# MCU.net
KiCad netlist of a schematic drawn in Altium Designer
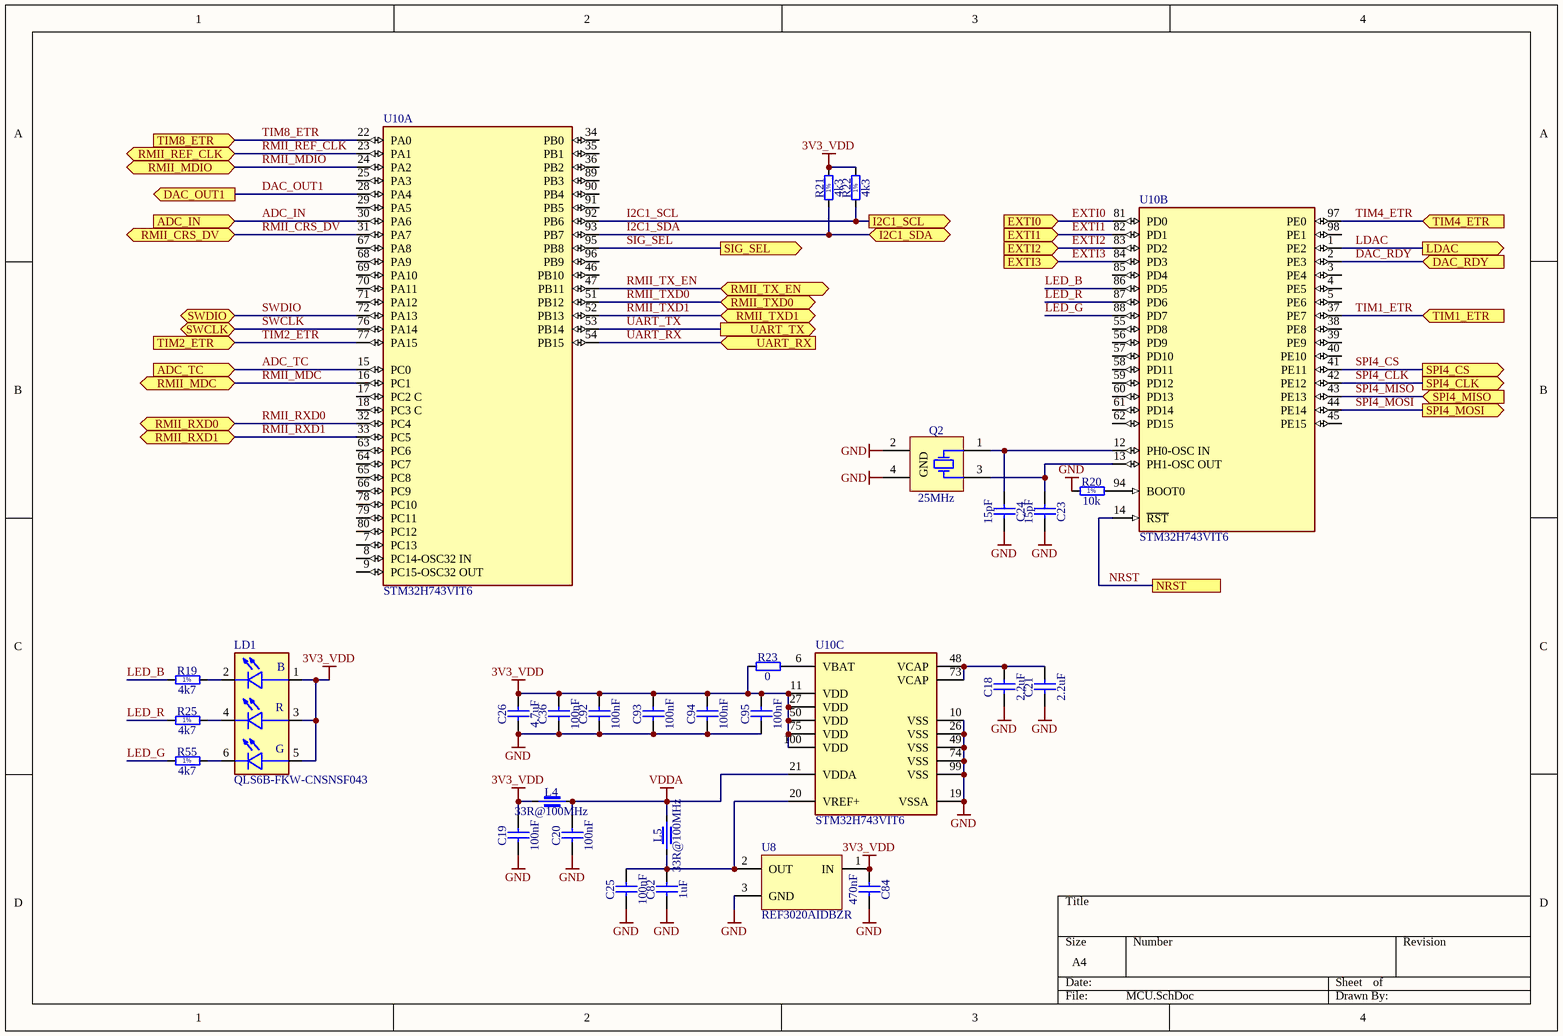
[diagram p0: MCU.SchDoc]

(export (version "E")
  (design (tool "Eeschema 10.0.6"))
  (components
    (comp (ref "C18")
      (value "2.2uF")
      (footprint "CAPC1608X87N")
      (description "Non-polarised capacitor")
      (fields
        (field (name "PART NUMBER") "CC0603_2.2UF_16V_10%_X5R")
        (field (name "VOLTAGE") "16V")
        (field (name "AUTHOR") "CERN DEM JLC")
      )
      (libsource (lib "Capacitors") (part "Capacitor - non polarized"))
    )
    (comp (ref "C19")
      (value "100nF")
      (footprint "CAPC1005X55N")
      (description "Non-polarised capacitor")
      (fields
        (field (name "PART NUMBER") "CC0402_100NF_16V_10%_X7R")
        (field (name "VOLTAGE") "16V")
        (field (name "AUTHOR") "CERN DEM JLC")
      )
      (libsource (lib "Capacitors") (part "Capacitor - non polarized"))
    )
    (comp (ref "C20")
      (value "100nF")
      (footprint "CAPC1005X55N")
      (description "Non-polarised capacitor")
      (fields
        (field (name "PART NUMBER") "CC0402_100NF_16V_10%_X7R")
        (field (name "VOLTAGE") "16V")
        (field (name "AUTHOR") "CERN DEM JLC")
      )
      (libsource (lib "Capacitors") (part "Capacitor - non polarized"))
    )
    (comp (ref "C21")
      (value "2.2uF")
      (footprint "CAPC1608X87N")
      (description "Non-polarised capacitor")
      (fields
        (field (name "PART NUMBER") "CC0603_2.2UF_16V_10%_X5R")
        (field (name "VOLTAGE") "16V")
        (field (name "AUTHOR") "CERN DEM JLC")
      )
      (libsource (lib "Capacitors") (part "Capacitor - non polarized"))
    )
    (comp (ref "C23")
      (value "15pF")
      (footprint "CAPC1005X55N")
      (description "Non-polarised capacitor")
      (fields
        (field (name "PART NUMBER") "CC0402_15PF_50V_5%_C0G")
        (field (name "VOLTAGE") "50V")
        (field (name "AUTHOR") "CERN DEM JLC")
      )
      (libsource (lib "Capacitors") (part "Capacitor - non polarized"))
    )
    (comp (ref "C24")
      (value "15pF")
      (footprint "CAPC1005X55N")
      (description "Non-polarised capacitor")
      (fields
        (field (name "PART NUMBER") "CC0402_15PF_50V_5%_C0G")
        (field (name "VOLTAGE") "50V")
        (field (name "AUTHOR") "CERN DEM JLC")
      )
      (libsource (lib "Capacitors") (part "Capacitor - non polarized"))
    )
    (comp (ref "C25")
      (value "100nF")
      (footprint "CAPC1005X55N")
      (description "Non-polarised capacitor")
      (fields
        (field (name "PART NUMBER") "CC0402_100NF_16V_10%_X7R")
        (field (name "VOLTAGE") "16V")
        (field (name "AUTHOR") "CERN DEM JLC")
      )
      (libsource (lib "Capacitors") (part "Capacitor - non polarized"))
    )
    (comp (ref "C26")
      (value "4.7uF")
      (footprint "CAPC1709X95N")
      (description "Non-polarised capacitor")
      (fields
        (field (name "PART NUMBER") "CC0603_4.7UF_16V_10%_X5R")
        (field (name "VOLTAGE") "16V")
        (field (name "AUTHOR") "CERN DEM JLC")
      )
      (libsource (lib "Capacitors") (part "Capacitor - non polarized"))
    )
    (comp (ref "C36")
      (value "100nF")
      (footprint "CAPC1005X55N")
      (description "Non-polarised capacitor")
      (fields
        (field (name "PART NUMBER") "CC0402_100NF_16V_10%_X7R")
        (field (name "VOLTAGE") "16V")
        (field (name "AUTHOR") "CERN DEM JLC")
      )
      (libsource (lib "Capacitors") (part "Capacitor - non polarized"))
    )
    (comp (ref "C82")
      (value "1uF")
      (footprint "CAPC1005X55N")
      (description "Non-polarised capacitor")
      (fields
        (field (name "PART NUMBER") "CC0402_1UF_16V_10%_X5R")
        (field (name "VOLTAGE") "16V")
        (field (name "AUTHOR") "CERN DEM JLC")
      )
      (libsource (lib "Capacitors") (part "Capacitor - non polarized"))
    )
    (comp (ref "C84")
      (value "470nF")
      (footprint "CAPC1005X55N")
      (description "Non-polarised capacitor")
      (fields
        (field (name "PART NUMBER") "CC0402_470NF_16V_10%_X5R")
        (field (name "VOLTAGE") "16V")
        (field (name "AUTHOR") "CERN DEM JLC")
      )
      (libsource (lib "Capacitors") (part "Capacitor - non polarized"))
    )
    (comp (ref "C92")
      (value "100nF")
      (footprint "CAPC1005X55N")
      (description "Non-polarised capacitor")
      (fields
        (field (name "PART NUMBER") "CC0402_100NF_16V_10%_X7R")
        (field (name "VOLTAGE") "16V")
        (field (name "AUTHOR") "CERN DEM JLC")
      )
      (libsource (lib "Capacitors") (part "Capacitor - non polarized"))
    )
    (comp (ref "C93")
      (value "100nF")
      (footprint "CAPC1005X55N")
      (description "Non-polarised capacitor")
      (fields
        (field (name "PART NUMBER") "CC0402_100NF_16V_10%_X7R")
        (field (name "VOLTAGE") "16V")
        (field (name "AUTHOR") "CERN DEM JLC")
      )
      (libsource (lib "Capacitors") (part "Capacitor - non polarized"))
    )
    (comp (ref "C94")
      (value "100nF")
      (footprint "CAPC1005X55N")
      (description "Non-polarised capacitor")
      (fields
        (field (name "PART NUMBER") "CC0402_100NF_16V_10%_X7R")
        (field (name "VOLTAGE") "16V")
        (field (name "AUTHOR") "CERN DEM JLC")
      )
      (libsource (lib "Capacitors") (part "Capacitor - non polarized"))
    )
    (comp (ref "C95")
      (value "100nF")
      (footprint "CAPC1005X55N")
      (description "Non-polarised capacitor")
      (fields
        (field (name "PART NUMBER") "CC0402_100NF_16V_10%_X7R")
        (field (name "VOLTAGE") "16V")
        (field (name "AUTHOR") "CERN DEM JLC")
      )
      (libsource (lib "Capacitors") (part "Capacitor - non polarized"))
    )
    (comp (ref "L4")
      (value "33R@100MHz")
      (footprint "INDC1005X55N")
      (fields
        (field (name "PART NUMBER") "IND0402_MURATA_BLM15PX330SN1D")
        (field (name "POWER") "3A")
        (field (name "TOLERANCE") "±25%")
        (field (name "AUTHOR") "CERN DEM JMW")
      )
      (libsource (lib "") (part "Ferrite Bead_1"))
    )
    (comp (ref "L5")
      (value "33R@100MHz")
      (footprint "INDC1005X55N")
      (fields
        (field (name "PART NUMBER") "IND0402_MURATA_BLM15PX330SN1D")
        (field (name "POWER") "3A")
        (field (name "TOLERANCE") "±25%")
        (field (name "AUTHOR") "CERN DEM JMW")
      )
      (libsource (lib "Inductors & Transformers") (part "Ferrite Bead"))
    )
    (comp (ref "LD1")
      (value "QLS6B-FKW-CNSNSF043")
      (footprint "LED_QLS6B-FKW-CNSNSF043")
      (fields (field (name "MF") "Cree Inc."))
      (libsource (lib "QLS6B-FKW-CNSNSF043") (part "QLS6B-FKW-CNSNSF043"))
    )
    (comp (ref "Q2")
      (value "25MHz")
      (footprint "XTAL_EPSON_TSX-3225")
      (description "Crystal 4 pins 1=XTAL Control 2=GND3=XTAL 4=GND")
      (fields
        (field (name "PART NUMBER") "XTAL_25MHZ_EPSON_TSX-3225 25.0000MF10Z-AC")
        (field (name "MANUFACTURER") "EPSON")
        (field (name "AUTHOR") "CERN DEM JLC")
      )
      (libsource (lib "ICs And Semiconductors") (part "Quartz Crystal 1X 2GND 3X 4GND"))
    )
    (comp (ref "R19")
      (value "4k7")
      (footprint "RESC1005X40N")
      (description "Resistor - 1%")
      (fields
        (field (name "PART NUMBER") "R0402_4K7_1%_0.0625W_100PPM")
        (field (name "POWER") "0.0625W")
        (field (name "AUTHOR") "CERN DEM JLC")
      )
      (libsource (lib "Resistors") (part "Resistor - 1%"))
    )
    (comp (ref "R20")
      (value "10k")
      (footprint "RESC1005X40N")
      (description "Resistor - 1%")
      (fields
        (field (name "PART NUMBER") "R0402_10K_1%_0.0625W_100PPM")
        (field (name "POWER") "0.0625W")
        (field (name "AUTHOR") "CERN DEM JLC")
      )
      (libsource (lib "Resistors") (part "Resistor - 1%"))
    )
    (comp (ref "R21")
      (value "4k3")
      (footprint "RESC1005X40N")
      (description "Resistor - 1%")
      (fields
        (field (name "PART NUMBER") "R0402_4K3_1%_0.0625W_100PPM")
        (field (name "POWER") "0.0625W")
        (field (name "AUTHOR") "CERN DEM JLC")
      )
      (libsource (lib "Resistors") (part "Resistor - 1%"))
    )
    (comp (ref "R22")
      (value "4k3")
      (footprint "RESC1005X40N")
      (description "Resistor - 1%")
      (fields
        (field (name "PART NUMBER") "R0402_4K3_1%_0.0625W_100PPM")
        (field (name "POWER") "0.0625W")
        (field (name "AUTHOR") "CERN DEM JLC")
      )
      (libsource (lib "Resistors") (part "Resistor - 1%"))
    )
    (comp (ref "R23")
      (value "0")
      (footprint "RESC1005X40N")
      (description "Resistor")
      (fields
        (field (name "PART NUMBER") "R0402_0R_JUMPER")
        (field (name "MANUFACTURER") "GENERIC")
        (field (name "AUTHOR") "CERN DEM JLC")
      )
      (libsource (lib "Resistors") (part "Resistor"))
    )
    (comp (ref "R25")
      (value "4k7")
      (footprint "RESC1005X40N")
      (description "Resistor - 1%")
      (fields
        (field (name "PART NUMBER") "R0402_4K7_1%_0.0625W_100PPM")
        (field (name "POWER") "0.0625W")
        (field (name "AUTHOR") "CERN DEM JLC")
      )
      (libsource (lib "Resistors") (part "Resistor - 1%"))
    )
    (comp (ref "R55")
      (value "4k7")
      (footprint "RESC1005X40N")
      (description "Resistor - 1%")
      (fields
        (field (name "PART NUMBER") "R0402_4K7_1%_0.0625W_100PPM")
        (field (name "POWER") "0.0625W")
        (field (name "AUTHOR") "CERN DEM JLC")
      )
      (libsource (lib "Resistors") (part "Resistor - 1%"))
    )
    (comp (ref "U8")
      (value "REF3020AIDBZR")
      (footprint "DBZ0003A_L")
      (fields (field (name "MANUFACTURER") "Texas Instruments"))
      (libsource (lib "Altium Content Vault") (part "TI-REF3020DBZ3"))
    )
    (comp (ref "U10")
      (value "STM32H743VIT6")
      (footprint "FP-LQFP100-1L-MFG")
      (description "IC MCU 32BIT 2MB FLASH 100LQFP")
      (fields
        (field (name "OCTOPART") "https://octopart.com/stm32h743vit6-stmicroelectronics-76372527")
        (field (name "MANUFACTURER") "STMicroelectronics")
      )
      (libsource (lib "Altium Content Vault") (part "01082ce2885d1d16a22823c45526fe6"))
    )
  )
  (nets
    (net (code "1") (name "/ADC_IN") (class "Default")
      (node (ref "U10") (pin "30") (pinfunction "PA6_30") (pintype "bidirectional"))
    )
    (net (code "2") (name "/ADC_TC") (class "Default")
      (node (ref "U10") (pin "15") (pinfunction "PC0_15") (pintype "bidirectional"))
    )
    (net (code "3") (name "/DAC_OUT1") (class "Default")
      (node (ref "U10") (pin "28") (pinfunction "PA4_28") (pintype "bidirectional"))
    )
    (net (code "4") (name "/DAC_RDY") (class "Default")
      (node (ref "U10") (pin "2") (pinfunction "PE3_2") (pintype "bidirectional"))
    )
    (net (code "5") (name "/EXTI0") (class "Default")
      (node (ref "U10") (pin "81") (pinfunction "PD0_81") (pintype "bidirectional"))
    )
    (net (code "6") (name "/EXTI1") (class "Default")
      (node (ref "U10") (pin "82") (pinfunction "PD1_82") (pintype "bidirectional"))
    )
    (net (code "7") (name "/EXTI2") (class "Default")
      (node (ref "U10") (pin "83") (pinfunction "PD2_83") (pintype "bidirectional"))
    )
    (net (code "8") (name "/EXTI3") (class "Default")
      (node (ref "U10") (pin "84") (pinfunction "PD3_84") (pintype "bidirectional"))
    )
    (net (code "9") (name "/I2C1_SCL") (class "Default")
      (node (ref "R22") (pin "1") (pinfunction "1_1") (pintype "passive"))
      (node (ref "U10") (pin "92") (pinfunction "PB6_92") (pintype "bidirectional"))
    )
    (net (code "10") (name "/I2C1_SDA") (class "Default")
      (node (ref "R21") (pin "1") (pinfunction "1_1") (pintype "passive"))
      (node (ref "U10") (pin "93") (pinfunction "PB7_93") (pintype "bidirectional"))
    )
    (net (code "11") (name "/LDAC") (class "Default")
      (node (ref "U10") (pin "1") (pinfunction "PE2_1") (pintype "bidirectional"))
    )
    (net (code "12") (name "/LED_B") (class "Default")
      (node (ref "R19") (pin "1") (pinfunction "1_1") (pintype "passive"))
      (node (ref "U10") (pin "86") (pinfunction "PD5_86") (pintype "bidirectional"))
    )
    (net (code "13") (name "/LED_G") (class "Default")
      (node (ref "R55") (pin "1") (pinfunction "1_1") (pintype "passive"))
      (node (ref "U10") (pin "88") (pinfunction "PD7_88") (pintype "bidirectional"))
    )
    (net (code "14") (name "/LED_R") (class "Default")
      (node (ref "R25") (pin "1") (pinfunction "1_1") (pintype "passive"))
      (node (ref "U10") (pin "87") (pinfunction "PD6_87") (pintype "bidirectional"))
    )
    (net (code "15") (name "/NRST") (class "Default")
      (node (ref "U10") (pin "14") (pinfunction "~{RST}_14") (pintype "input"))
    )
    (net (code "16") (name "/RMII_CRS_DV") (class "Default")
      (node (ref "U10") (pin "31") (pinfunction "PA7_31") (pintype "bidirectional"))
    )
    (net (code "17") (name "/RMII_MDC") (class "Default")
      (node (ref "U10") (pin "16") (pinfunction "PC1_16") (pintype "bidirectional"))
    )
    (net (code "18") (name "/RMII_MDIO") (class "Default")
      (node (ref "U10") (pin "24") (pinfunction "PA2_24") (pintype "bidirectional"))
    )
    (net (code "19") (name "/RMII_REF_CLK") (class "Default")
      (node (ref "U10") (pin "23") (pinfunction "PA1_23") (pintype "bidirectional"))
    )
    (net (code "20") (name "/RMII_RXD0") (class "Default")
      (node (ref "U10") (pin "32") (pinfunction "PC4_32") (pintype "bidirectional"))
    )
    (net (code "21") (name "/RMII_RXD1") (class "Default")
      (node (ref "U10") (pin "33") (pinfunction "PC5_33") (pintype "bidirectional"))
    )
    (net (code "22") (name "/RMII_TXD0") (class "Default")
      (node (ref "U10") (pin "51") (pinfunction "PB12_51") (pintype "bidirectional"))
    )
    (net (code "23") (name "/RMII_TXD1") (class "Default")
      (node (ref "U10") (pin "52") (pinfunction "PB13_52") (pintype "bidirectional"))
    )
    (net (code "24") (name "/RMII_TX_EN") (class "Default")
      (node (ref "U10") (pin "47") (pinfunction "PB11_47") (pintype "bidirectional"))
    )
    (net (code "25") (name "/SIG_SEL") (class "Default")
      (node (ref "U10") (pin "95") (pinfunction "PB8_95") (pintype "bidirectional"))
    )
    (net (code "26") (name "/SPI4_CLK") (class "Default")
      (node (ref "U10") (pin "42") (pinfunction "PE12_42") (pintype "bidirectional"))
    )
    (net (code "27") (name "/SPI4_CS") (class "Default")
      (node (ref "U10") (pin "41") (pinfunction "PE11_41") (pintype "bidirectional"))
    )
    (net (code "28") (name "/SPI4_MISO") (class "Default")
      (node (ref "U10") (pin "43") (pinfunction "PE13_43") (pintype "bidirectional"))
    )
    (net (code "29") (name "/SPI4_MOSI") (class "Default")
      (node (ref "U10") (pin "44") (pinfunction "PE14_44") (pintype "bidirectional"))
    )
    (net (code "30") (name "/SWCLK") (class "Default")
      (node (ref "U10") (pin "76") (pinfunction "PA14_76") (pintype "bidirectional"))
    )
    (net (code "31") (name "/SWDIO") (class "Default")
      (node (ref "U10") (pin "72") (pinfunction "PA13_72") (pintype "bidirectional"))
    )
    (net (code "32") (name "/TIM1_ETR") (class "Default")
      (node (ref "U10") (pin "37") (pinfunction "PE7_37") (pintype "bidirectional"))
    )
    (net (code "33") (name "/TIM2_ETR") (class "Default")
      (node (ref "U10") (pin "77") (pinfunction "PA15_77") (pintype "bidirectional"))
    )
    (net (code "34") (name "/TIM4_ETR") (class "Default")
      (node (ref "U10") (pin "97") (pinfunction "PE0_97") (pintype "bidirectional"))
    )
    (net (code "35") (name "/TIM8_ETR") (class "Default")
      (node (ref "U10") (pin "22") (pinfunction "PA0_22") (pintype "bidirectional"))
    )
    (net (code "36") (name "/UART_RX") (class "Default")
      (node (ref "U10") (pin "54") (pinfunction "PB15_54") (pintype "bidirectional"))
    )
    (net (code "37") (name "/UART_TX") (class "Default")
      (node (ref "U10") (pin "53") (pinfunction "PB14_53") (pintype "bidirectional"))
    )
    (net (code "38") (name "3V3_VDD") (class "Default")
      (node (ref "C19") (pin "2") (pinfunction "2_2") (pintype "passive"))
      (node (ref "C26") (pin "2") (pinfunction "2_2") (pintype "passive"))
      (node (ref "C36") (pin "2") (pinfunction "2_2") (pintype "passive"))
      (node (ref "C84") (pin "2") (pinfunction "2_2") (pintype "passive"))
      (node (ref "C92") (pin "2") (pinfunction "2_2") (pintype "passive"))
      (node (ref "C93") (pin "2") (pinfunction "2_2") (pintype "passive"))
      (node (ref "C94") (pin "2") (pinfunction "2_2") (pintype "passive"))
      (node (ref "C95") (pin "2") (pinfunction "2_2") (pintype "passive"))
      (node (ref "L4") (pin "1") (pinfunction "1_1") (pintype "passive"))
      (node (ref "LD1") (pin "1") (pinfunction "BLUE_ANODE_1") (pintype "passive"))
      (node (ref "LD1") (pin "3") (pinfunction "RED_ANODE_3") (pintype "passive"))
      (node (ref "LD1") (pin "5") (pinfunction "GREEN_ANODE_5") (pintype "passive"))
      (node (ref "R21") (pin "2") (pinfunction "2_2") (pintype "passive"))
      (node (ref "R22") (pin "2") (pinfunction "2_2") (pintype "passive"))
      (node (ref "R23") (pin "1") (pinfunction "1_1") (pintype "passive"))
      (node (ref "U10") (pin "100") (pinfunction "VDD_100") (pintype "power_in"))
      (node (ref "U10") (pin "11") (pinfunction "VDD_11") (pintype "power_in"))
      (node (ref "U10") (pin "27") (pinfunction "VDD_27") (pintype "power_in"))
      (node (ref "U10") (pin "50") (pinfunction "VDD_50") (pintype "power_in"))
      (node (ref "U10") (pin "75") (pinfunction "VDD_75") (pintype "power_in"))
      (node (ref "U8") (pin "1") (pinfunction "IN_1") (pintype "power_in"))
    )
    (net (code "39") (name "GND") (class "Default")
      (node (ref "C18") (pin "1") (pinfunction "1_1") (pintype "passive"))
      (node (ref "C19") (pin "1") (pinfunction "1_1") (pintype "passive"))
      (node (ref "C20") (pin "1") (pinfunction "1_1") (pintype "passive"))
      (node (ref "C21") (pin "1") (pinfunction "1_1") (pintype "passive"))
      (node (ref "C23") (pin "1") (pinfunction "1_1") (pintype "passive"))
      (node (ref "C24") (pin "1") (pinfunction "1_1") (pintype "passive"))
      (node (ref "C25") (pin "1") (pinfunction "1_1") (pintype "passive"))
      (node (ref "C26") (pin "1") (pinfunction "1_1") (pintype "passive"))
      (node (ref "C36") (pin "1") (pinfunction "1_1") (pintype "passive"))
      (node (ref "C82") (pin "1") (pinfunction "1_1") (pintype "passive"))
      (node (ref "C84") (pin "1") (pinfunction "1_1") (pintype "passive"))
      (node (ref "C92") (pin "1") (pinfunction "1_1") (pintype "passive"))
      (node (ref "C93") (pin "1") (pinfunction "1_1") (pintype "passive"))
      (node (ref "C94") (pin "1") (pinfunction "1_1") (pintype "passive"))
      (node (ref "C95") (pin "1") (pinfunction "1_1") (pintype "passive"))
      (node (ref "Q2") (pin "2") (pinfunction "GND_2") (pintype "power_in"))
      (node (ref "Q2") (pin "4") (pinfunction "GND_4") (pintype "power_in"))
      (node (ref "R20") (pin "1") (pinfunction "1_1") (pintype "passive"))
      (node (ref "U10") (pin "10") (pinfunction "VSS_10") (pintype "power_in"))
      (node (ref "U10") (pin "19") (pinfunction "VSSA_19") (pintype "power_in"))
      (node (ref "U10") (pin "26") (pinfunction "VSS_26") (pintype "power_in"))
      (node (ref "U10") (pin "49") (pinfunction "VSS_49") (pintype "power_in"))
      (node (ref "U10") (pin "74") (pinfunction "VSS_74") (pintype "power_in"))
      (node (ref "U10") (pin "99") (pinfunction "VSS_99") (pintype "power_in"))
      (node (ref "U8") (pin "3") (pinfunction "GND_3") (pintype "power_in"))
    )
    (net (code "40") (name "Net-(C18-Pad2)") (class "Default")
      (node (ref "C18") (pin "2") (pinfunction "2_2") (pintype "passive"))
      (node (ref "C21") (pin "2") (pinfunction "2_2") (pintype "passive"))
      (node (ref "U10") (pin "48") (pinfunction "VCAP_48") (pintype "passive"))
      (node (ref "U10") (pin "73") (pinfunction "VCAP_73") (pintype "passive"))
    )
    (net (code "41") (name "Net-(LD1-BLUE_CATHODE)") (class "Default")
      (node (ref "LD1") (pin "2") (pinfunction "BLUE_CATHODE_2") (pintype "passive"))
      (node (ref "R19") (pin "2") (pinfunction "2_2") (pintype "passive"))
    )
    (net (code "42") (name "Net-(LD1-GREEN_CATHODE)") (class "Default")
      (node (ref "LD1") (pin "6") (pinfunction "GREEN_CATHODE_6") (pintype "passive"))
      (node (ref "R55") (pin "2") (pinfunction "2_2") (pintype "passive"))
    )
    (net (code "43") (name "Net-(LD1-RED_CATHODE)") (class "Default")
      (node (ref "LD1") (pin "4") (pinfunction "RED_CATHODE_4") (pintype "passive"))
      (node (ref "R25") (pin "2") (pinfunction "2_2") (pintype "passive"))
    )
    (net (code "44") (name "Net-(U10B-BOOT0)") (class "Default")
      (node (ref "R20") (pin "2") (pinfunction "2_2") (pintype "passive"))
      (node (ref "U10") (pin "94") (pinfunction "BOOT0_94") (pintype "input"))
    )
    (net (code "45") (name "Net-(U10B-PH0-OSC_IN)") (class "Default")
      (node (ref "C24") (pin "2") (pinfunction "2_2") (pintype "passive"))
      (node (ref "Q2") (pin "1") (pinfunction "X_1") (pintype "passive"))
      (node (ref "U10") (pin "12") (pinfunction "PH0-OSC_IN_12") (pintype "bidirectional"))
    )
    (net (code "46") (name "Net-(U10B-PH1-OSC_OUT)") (class "Default")
      (node (ref "C23") (pin "2") (pinfunction "2_2") (pintype "passive"))
      (node (ref "Q2") (pin "3") (pinfunction "X_3") (pintype "passive"))
      (node (ref "U10") (pin "13") (pinfunction "PH1-OSC_OUT_13") (pintype "bidirectional"))
    )
    (net (code "47") (name "Net-(U10C-VBAT)") (class "Default")
      (node (ref "R23") (pin "2") (pinfunction "2_2") (pintype "passive"))
      (node (ref "U10") (pin "6") (pinfunction "VBAT_6") (pintype "power_in"))
    )
    (net (code "48") (name "Net-(U10C-VREF+)") (class "Default")
      (node (ref "C25") (pin "2") (pinfunction "2_2") (pintype "passive"))
      (node (ref "C82") (pin "2") (pinfunction "2_2") (pintype "passive"))
      (node (ref "L5") (pin "1") (pinfunction "1_1") (pintype "passive"))
      (node (ref "U10") (pin "20") (pinfunction "VREF+_20") (pintype "power_in"))
      (node (ref "U8") (pin "2") (pinfunction "OUT_2") (pintype "power_in"))
    )
    (net (code "49") (name "VDDA") (class "Default")
      (node (ref "C20") (pin "2") (pinfunction "2_2") (pintype "passive"))
      (node (ref "L4") (pin "2") (pinfunction "2_2") (pintype "passive"))
      (node (ref "L5") (pin "2") (pinfunction "2_2") (pintype "passive"))
      (node (ref "U10") (pin "21") (pinfunction "VDDA_21") (pintype "power_in"))
    )
    (net (code "50") (name "unconnected-(U10A-PA3-Pad25)") (class "Default")
      (node (ref "U10") (pin "25") (pinfunction "PA3_25") (pintype "bidirectional"))
    )
    (net (code "51") (name "unconnected-(U10A-PA5-Pad29)") (class "Default")
      (node (ref "U10") (pin "29") (pinfunction "PA5_29") (pintype "bidirectional"))
    )
    (net (code "52") (name "unconnected-(U10A-PA8-Pad67)") (class "Default")
      (node (ref "U10") (pin "67") (pinfunction "PA8_67") (pintype "bidirectional"))
    )
    (net (code "53") (name "unconnected-(U10A-PA9-Pad68)") (class "Default")
      (node (ref "U10") (pin "68") (pinfunction "PA9_68") (pintype "bidirectional"))
    )
    (net (code "54") (name "unconnected-(U10A-PA10-Pad69)") (class "Default")
      (node (ref "U10") (pin "69") (pinfunction "PA10_69") (pintype "bidirectional"))
    )
    (net (code "55") (name "unconnected-(U10A-PA11-Pad70)") (class "Default")
      (node (ref "U10") (pin "70") (pinfunction "PA11_70") (pintype "bidirectional"))
    )
    (net (code "56") (name "unconnected-(U10A-PA12-Pad71)") (class "Default")
      (node (ref "U10") (pin "71") (pinfunction "PA12_71") (pintype "bidirectional"))
    )
    (net (code "57") (name "unconnected-(U10A-PB0-Pad34)") (class "Default")
      (node (ref "U10") (pin "34") (pinfunction "PB0_34") (pintype "bidirectional"))
    )
    (net (code "58") (name "unconnected-(U10A-PB1-Pad35)") (class "Default")
      (node (ref "U10") (pin "35") (pinfunction "PB1_35") (pintype "bidirectional"))
    )
    (net (code "59") (name "unconnected-(U10A-PB2-Pad36)") (class "Default")
      (node (ref "U10") (pin "36") (pinfunction "PB2_36") (pintype "bidirectional"))
    )
    (net (code "60") (name "unconnected-(U10A-PB3-Pad89)") (class "Default")
      (node (ref "U10") (pin "89") (pinfunction "PB3_89") (pintype "bidirectional"))
    )
    (net (code "61") (name "unconnected-(U10A-PB4-Pad90)") (class "Default")
      (node (ref "U10") (pin "90") (pinfunction "PB4_90") (pintype "bidirectional"))
    )
    (net (code "62") (name "unconnected-(U10A-PB5-Pad91)") (class "Default")
      (node (ref "U10") (pin "91") (pinfunction "PB5_91") (pintype "bidirectional"))
    )
    (net (code "63") (name "unconnected-(U10A-PB9-Pad96)") (class "Default")
      (node (ref "U10") (pin "96") (pinfunction "PB9_96") (pintype "bidirectional"))
    )
    (net (code "64") (name "unconnected-(U10A-PB10-Pad46)") (class "Default")
      (node (ref "U10") (pin "46") (pinfunction "PB10_46") (pintype "bidirectional"))
    )
    (net (code "65") (name "unconnected-(U10A-PC2_C-Pad17)") (class "Default")
      (node (ref "U10") (pin "17") (pinfunction "PC2_C_17") (pintype "bidirectional"))
    )
    (net (code "66") (name "unconnected-(U10A-PC3_C-Pad18)") (class "Default")
      (node (ref "U10") (pin "18") (pinfunction "PC3_C_18") (pintype "bidirectional"))
    )
    (net (code "67") (name "unconnected-(U10A-PC6-Pad63)") (class "Default")
      (node (ref "U10") (pin "63") (pinfunction "PC6_63") (pintype "bidirectional"))
    )
    (net (code "68") (name "unconnected-(U10A-PC7-Pad64)") (class "Default")
      (node (ref "U10") (pin "64") (pinfunction "PC7_64") (pintype "bidirectional"))
    )
    (net (code "69") (name "unconnected-(U10A-PC8-Pad65)") (class "Default")
      (node (ref "U10") (pin "65") (pinfunction "PC8_65") (pintype "bidirectional"))
    )
    (net (code "70") (name "unconnected-(U10A-PC9-Pad66)") (class "Default")
      (node (ref "U10") (pin "66") (pinfunction "PC9_66") (pintype "bidirectional"))
    )
    (net (code "71") (name "unconnected-(U10A-PC10-Pad78)") (class "Default")
      (node (ref "U10") (pin "78") (pinfunction "PC10_78") (pintype "bidirectional"))
    )
    (net (code "72") (name "unconnected-(U10A-PC11-Pad79)") (class "Default")
      (node (ref "U10") (pin "79") (pinfunction "PC11_79") (pintype "bidirectional"))
    )
    (net (code "73") (name "unconnected-(U10A-PC12-Pad80)") (class "Default")
      (node (ref "U10") (pin "80") (pinfunction "PC12_80") (pintype "bidirectional"))
    )
    (net (code "74") (name "unconnected-(U10A-PC13-Pad7)") (class "Default")
      (node (ref "U10") (pin "7") (pinfunction "PC13_7") (pintype "bidirectional"))
    )
    (net (code "75") (name "unconnected-(U10A-PC14-OSC32_IN-Pad8)") (class "Default")
      (node (ref "U10") (pin "8") (pinfunction "PC14-OSC32_IN_8") (pintype "bidirectional"))
    )
    (net (code "76") (name "unconnected-(U10A-PC15-OSC32_OUT-Pad9)") (class "Default")
      (node (ref "U10") (pin "9") (pinfunction "PC15-OSC32_OUT_9") (pintype "bidirectional"))
    )
    (net (code "77") (name "unconnected-(U10B-PD4-Pad85)") (class "Default")
      (node (ref "U10") (pin "85") (pinfunction "PD4_85") (pintype "bidirectional"))
    )
    (net (code "78") (name "unconnected-(U10B-PD8-Pad55)") (class "Default")
      (node (ref "U10") (pin "55") (pinfunction "PD8_55") (pintype "bidirectional"))
    )
    (net (code "79") (name "unconnected-(U10B-PD9-Pad56)") (class "Default")
      (node (ref "U10") (pin "56") (pinfunction "PD9_56") (pintype "bidirectional"))
    )
    (net (code "80") (name "unconnected-(U10B-PD10-Pad57)") (class "Default")
      (node (ref "U10") (pin "57") (pinfunction "PD10_57") (pintype "bidirectional"))
    )
    (net (code "81") (name "unconnected-(U10B-PD11-Pad58)") (class "Default")
      (node (ref "U10") (pin "58") (pinfunction "PD11_58") (pintype "bidirectional"))
    )
    (net (code "82") (name "unconnected-(U10B-PD12-Pad59)") (class "Default")
      (node (ref "U10") (pin "59") (pinfunction "PD12_59") (pintype "bidirectional"))
    )
    (net (code "83") (name "unconnected-(U10B-PD13-Pad60)") (class "Default")
      (node (ref "U10") (pin "60") (pinfunction "PD13_60") (pintype "bidirectional"))
    )
    (net (code "84") (name "unconnected-(U10B-PD14-Pad61)") (class "Default")
      (node (ref "U10") (pin "61") (pinfunction "PD14_61") (pintype "bidirectional"))
    )
    (net (code "85") (name "unconnected-(U10B-PD15-Pad62)") (class "Default")
      (node (ref "U10") (pin "62") (pinfunction "PD15_62") (pintype "bidirectional"))
    )
    (net (code "86") (name "unconnected-(U10B-PE1-Pad98)") (class "Default")
      (node (ref "U10") (pin "98") (pinfunction "PE1_98") (pintype "bidirectional"))
    )
    (net (code "87") (name "unconnected-(U10B-PE4-Pad3)") (class "Default")
      (node (ref "U10") (pin "3") (pinfunction "PE4_3") (pintype "bidirectional"))
    )
    (net (code "88") (name "unconnected-(U10B-PE5-Pad4)") (class "Default")
      (node (ref "U10") (pin "4") (pinfunction "PE5_4") (pintype "bidirectional"))
    )
    (net (code "89") (name "unconnected-(U10B-PE6-Pad5)") (class "Default")
      (node (ref "U10") (pin "5") (pinfunction "PE6_5") (pintype "bidirectional"))
    )
    (net (code "90") (name "unconnected-(U10B-PE8-Pad38)") (class "Default")
      (node (ref "U10") (pin "38") (pinfunction "PE8_38") (pintype "bidirectional"))
    )
    (net (code "91") (name "unconnected-(U10B-PE9-Pad39)") (class "Default")
      (node (ref "U10") (pin "39") (pinfunction "PE9_39") (pintype "bidirectional"))
    )
    (net (code "92") (name "unconnected-(U10B-PE10-Pad40)") (class "Default")
      (node (ref "U10") (pin "40") (pinfunction "PE10_40") (pintype "bidirectional"))
    )
    (net (code "93") (name "unconnected-(U10B-PE15-Pad45)") (class "Default")
      (node (ref "U10") (pin "45") (pinfunction "PE15_45") (pintype "bidirectional"))
    )
  )
)
